# MicroSd.net
KiCad netlist of a schematic drawn in Altium Designer
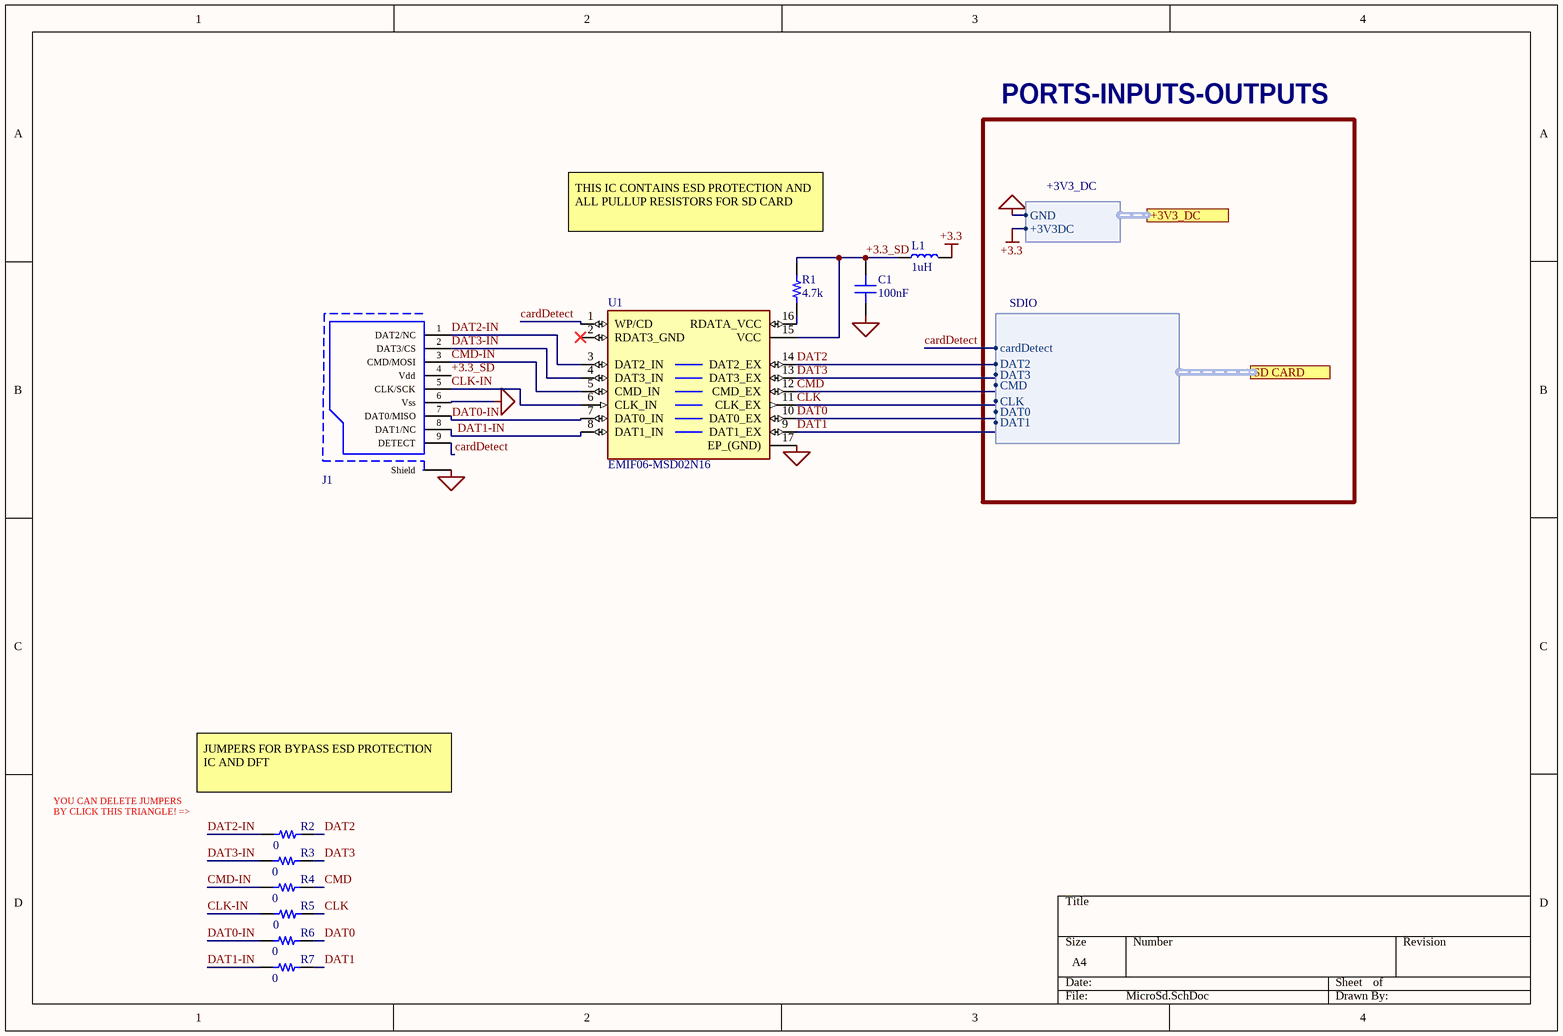
[diagram p0: MicroSd.SchDoc]

(export (version "E")
  (design (tool "Eeschema 10.0.6"))
  (components
    (comp (ref "C1")
      (value "100nF")
      (footprint "CAP 0603_1608")
      (description "SMT Capacitor")
      (libsource (lib "Capacitor") (part "Cap 0603"))
    )
    (comp (ref "J1")
      (value "Micro SD")
      (footprint "TFP-09-2-12B")
      (fields (field (name "PARTNUMBER") "TFP-09-2-12B"))
      (libsource (lib "Conn Card") (part "Micro SD TFP-09-2-12B"))
    )
    (comp (ref "L1")
      (value "1uH")
      (footprint "IND 0805_2012")
      (description "SMT Inductor")
      (libsource (lib "Inductor") (part "Ind 0805"))
    )
    (comp (ref "R1")
      (value "4.7k")
      (footprint "RES 0603_1608")
      (description "SMT Resistor")
      (libsource (lib "Resistor") (part "Res 0603"))
    )
    (comp (ref "R2")
      (value "0")
      (footprint "RES 0805_2012")
      (description "SMT Resistor")
      (libsource (lib "Resistor") (part "Res 0805"))
    )
    (comp (ref "R3")
      (value "0")
      (footprint "RES 0805_2012")
      (description "SMT Resistor")
      (libsource (lib "Resistor") (part "Res 0805"))
    )
    (comp (ref "R4")
      (value "0")
      (footprint "RES 0805_2012")
      (description "SMT Resistor")
      (libsource (lib "Resistor") (part "Res 0805"))
    )
    (comp (ref "R5")
      (value "0")
      (footprint "RES 0805_2012")
      (description "SMT Resistor")
      (libsource (lib "Resistor") (part "Res 0805"))
    )
    (comp (ref "R6")
      (value "0")
      (footprint "RES 0805_2012")
      (description "SMT Resistor")
      (libsource (lib "Resistor") (part "Res 0805"))
    )
    (comp (ref "R7")
      (value "0")
      (footprint "RES 0805_2012")
      (description "SMT Resistor")
      (libsource (lib "Resistor") (part "Res 0805"))
    )
    (comp (ref "U1")
      (value "EMIF06-MSD02N16")
      (footprint "EMIF06MSD02N16")
      (description "RC (Pi) EMI Filter 2nd Order Low Pass 6 Channel R = 45Ohms, C = 20pF (Total) 16-UFDFN Exposed Pad")
      (fields (field (name "MF") "STMicroelectronics"))
      (libsource (lib "EMIF06-MSD02N16") (part "EMIF06-MSD02N16"))
    )
  )
  (nets
    (net (code "3") (name "+3.3") (class "Default")
      (node (ref "L1") (pin "2") (pinfunction "2_2") (pintype "passive"))
    )
    (net (code "4") (name "/+3.3_SD") (class "Default")
      (node (ref "C1") (pin "2") (pinfunction "2_2") (pintype "passive"))
      (node (ref "J1") (pin "4") (pinfunction "Vdd_4") (pintype "passive"))
      (node (ref "L1") (pin "1") (pinfunction "1_1") (pintype "passive"))
      (node (ref "R1") (pin "2") (pinfunction "2_2") (pintype "passive"))
      (node (ref "U1") (pin "15") (pinfunction "VCC_15") (pintype "power_in"))
    )
    (net (code "5") (name "/CLK") (class "Default")
      (node (ref "R5") (pin "2") (pinfunction "2_2") (pintype "passive"))
      (node (ref "U1") (pin "11") (pinfunction "CLK_EX_11") (pintype "output"))
    )
    (net (code "6") (name "/CLK-IN") (class "Default")
      (node (ref "J1") (pin "5") (pinfunction "CLK/SCK_5") (pintype "passive"))
      (node (ref "R5") (pin "1") (pinfunction "1_1") (pintype "passive"))
      (node (ref "U1") (pin "6") (pinfunction "CLK_IN_6") (pintype "input"))
    )
    (net (code "7") (name "/CMD") (class "Default")
      (node (ref "R4") (pin "2") (pinfunction "2_2") (pintype "passive"))
      (node (ref "U1") (pin "12") (pinfunction "CMD_EX_12") (pintype "bidirectional"))
    )
    (net (code "8") (name "/CMD-IN") (class "Default")
      (node (ref "J1") (pin "3") (pinfunction "CMD/MOSI_3") (pintype "passive"))
      (node (ref "R4") (pin "1") (pinfunction "1_1") (pintype "passive"))
      (node (ref "U1") (pin "5") (pinfunction "CMD_IN_5") (pintype "bidirectional"))
    )
    (net (code "9") (name "/DAT0") (class "Default")
      (node (ref "R6") (pin "2") (pinfunction "2_2") (pintype "passive"))
      (node (ref "U1") (pin "10") (pinfunction "DAT0_EX_10") (pintype "bidirectional"))
    )
    (net (code "10") (name "/DAT0-IN") (class "Default")
      (node (ref "J1") (pin "7") (pinfunction "DAT0/MISO_7") (pintype "passive"))
      (node (ref "R6") (pin "1") (pinfunction "1_1") (pintype "passive"))
      (node (ref "U1") (pin "7") (pinfunction "DAT0_IN_7") (pintype "bidirectional"))
    )
    (net (code "11") (name "/DAT1") (class "Default")
      (node (ref "R7") (pin "2") (pinfunction "2_2") (pintype "passive"))
      (node (ref "U1") (pin "9") (pinfunction "DAT1_EX_9") (pintype "bidirectional"))
    )
    (net (code "12") (name "/DAT1-IN") (class "Default")
      (node (ref "J1") (pin "8") (pinfunction "DAT1/NC_8") (pintype "passive"))
      (node (ref "R7") (pin "1") (pinfunction "1_1") (pintype "passive"))
      (node (ref "U1") (pin "8") (pinfunction "DAT1_IN_8") (pintype "bidirectional"))
    )
    (net (code "13") (name "/DAT2") (class "Default")
      (node (ref "R2") (pin "2") (pinfunction "2_2") (pintype "passive"))
      (node (ref "U1") (pin "14") (pinfunction "DAT2_EX_14") (pintype "bidirectional"))
    )
    (net (code "14") (name "/DAT2-IN") (class "Default")
      (node (ref "J1") (pin "1") (pinfunction "DAT2/NC_1") (pintype "passive"))
      (node (ref "R2") (pin "1") (pinfunction "1_1") (pintype "passive"))
      (node (ref "U1") (pin "3") (pinfunction "DAT2_IN_3") (pintype "bidirectional"))
    )
    (net (code "15") (name "/DAT3") (class "Default")
      (node (ref "R3") (pin "2") (pinfunction "2_2") (pintype "passive"))
      (node (ref "U1") (pin "13") (pinfunction "DAT3_EX_13") (pintype "bidirectional"))
    )
    (net (code "16") (name "/DAT3-IN") (class "Default")
      (node (ref "J1") (pin "2") (pinfunction "DAT3/CS_2") (pintype "passive"))
      (node (ref "R3") (pin "1") (pinfunction "1_1") (pintype "passive"))
      (node (ref "U1") (pin "4") (pinfunction "DAT3_IN_4") (pintype "bidirectional"))
    )
    (net (code "17") (name "/cardDetect") (class "Default")
      (node (ref "J1") (pin "9") (pinfunction "DETECT_9") (pintype "passive"))
      (node (ref "U1") (pin "1") (pinfunction "WP/CD_1") (pintype "bidirectional"))
    )
    (net (code "20") (name "IGND") (class "Default")
      (node (ref "C1") (pin "1") (pinfunction "1_1") (pintype "passive"))
      (node (ref "J1") (pin "10") (pinfunction "Shield_10") (pintype "passive"))
      (node (ref "J1") (pin "6") (pinfunction "Vss_6") (pintype "passive"))
      (node (ref "U1") (pin "17") (pinfunction "EP_(GND)_17") (pintype "power_in"))
    )
    (net (code "21") (name "Net-(U1-RDATA_VCC)") (class "Default")
      (node (ref "R1") (pin "1") (pinfunction "1_1") (pintype "passive"))
      (node (ref "U1") (pin "16") (pinfunction "RDATA_VCC_16") (pintype "bidirectional"))
    )
    (net (code "22") (name "unconnected-(U1-RDAT3_GND-Pad2)") (class "Default")
      (node (ref "U1") (pin "2") (pinfunction "RDAT3_GND_2") (pintype "bidirectional+no_connect"))
    )
  )
)
